# Ematches.net
KiCad netlist of a schematic drawn in Altium Designer
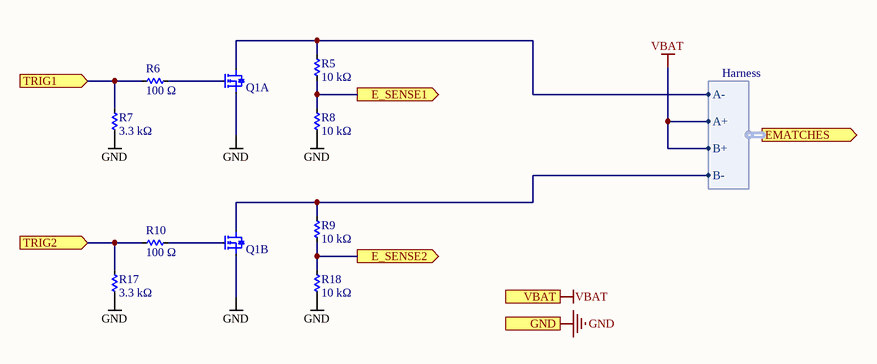
[diagram p0: Ematches.SchDoc]

(export (version "E")
  (design (tool "Eeschema 10.0.6"))
  (components
    (comp (ref "Q1")
      (value "Symbol")
      (footprint "POWERPAK_1212-8_DUAL")
      (description "MOSFET 2N-CH 20V 25A PPAK 1212-8")
      (fields
        (field (name "MANUFACTURER") "Vishay Siliconix")
        (field (name "MANUFACTURER PART NUMBER") "SI7232DN-T1-GE3")
      )
      (libsource (lib "Stanford Student Space Initiative") (part "Symbol"))
    )
    (comp (ref "R5")
      (value "311-10.0KHRCT-ND")
      (footprint "R0603")
      (description "RES SMD 10K OHM 1% 1/10W 0603")
      (fields
        (field (name "MANUFACTURER PART NUMBER") "RC0603FR-0710KL")
        (field (name "MANUFACTURER") "Yageo")
        (field (name "RESISTANCE") "10 kΩ")
      )
      (libsource (lib "Stanford Student Space Initiative") (part "__template_resistor"))
    )
    (comp (ref "R6")
      (value "311-100HRCT-ND")
      (footprint "R0603")
      (description "RES SMD 100 OHM 1% 1/10W 0603")
      (fields
        (field (name "MANUFACTURER PART NUMBER") "RC0603FR-07100RL")
        (field (name "MANUFACTURER") "Yageo")
        (field (name "RESISTANCE") "100 Ω")
      )
      (libsource (lib "Stanford Student Space Initiative") (part "__template_resistor"))
    )
    (comp (ref "R7")
      (value "311-3.30KHRCT-ND")
      (footprint "R0603")
      (description "RES SMD 3.3K OHM 1% 1/10W 0603")
      (fields
        (field (name "MANUFACTURER PART NUMBER") "RC0603FR-073K3L")
        (field (name "MANUFACTURER") "Yageo")
        (field (name "RESISTANCE") "3.3 kΩ")
      )
      (libsource (lib "Stanford Student Space Initiative") (part "__template_resistor"))
    )
    (comp (ref "R8")
      (value "311-10.0KHRCT-ND")
      (footprint "R0603")
      (description "RES SMD 10K OHM 1% 1/10W 0603")
      (fields
        (field (name "MANUFACTURER PART NUMBER") "RC0603FR-0710KL")
        (field (name "MANUFACTURER") "Yageo")
        (field (name "RESISTANCE") "10 kΩ")
      )
      (libsource (lib "Stanford Student Space Initiative") (part "__template_resistor"))
    )
    (comp (ref "R9")
      (value "311-10.0KHRCT-ND")
      (footprint "R0603")
      (description "RES SMD 10K OHM 1% 1/10W 0603")
      (fields
        (field (name "MANUFACTURER PART NUMBER") "RC0603FR-0710KL")
        (field (name "MANUFACTURER") "Yageo")
        (field (name "RESISTANCE") "10 kΩ")
      )
      (libsource (lib "Stanford Student Space Initiative") (part "__template_resistor"))
    )
    (comp (ref "R10")
      (value "311-100HRCT-ND")
      (footprint "R0603")
      (description "RES SMD 100 OHM 1% 1/10W 0603")
      (fields
        (field (name "MANUFACTURER PART NUMBER") "RC0603FR-07100RL")
        (field (name "MANUFACTURER") "Yageo")
        (field (name "RESISTANCE") "100 Ω")
      )
      (libsource (lib "Stanford Student Space Initiative") (part "__template_resistor"))
    )
    (comp (ref "R17")
      (value "311-3.30KHRCT-ND")
      (footprint "R0603")
      (description "RES SMD 3.3K OHM 1% 1/10W 0603")
      (fields
        (field (name "MANUFACTURER PART NUMBER") "RC0603FR-073K3L")
        (field (name "MANUFACTURER") "Yageo")
        (field (name "RESISTANCE") "3.3 kΩ")
      )
      (libsource (lib "Stanford Student Space Initiative") (part "__template_resistor"))
    )
    (comp (ref "R18")
      (value "311-10.0KHRCT-ND")
      (footprint "R0603")
      (description "RES SMD 10K OHM 1% 1/10W 0603")
      (fields
        (field (name "MANUFACTURER PART NUMBER") "RC0603FR-0710KL")
        (field (name "MANUFACTURER") "Yageo")
        (field (name "RESISTANCE") "10 kΩ")
      )
      (libsource (lib "Stanford Student Space Initiative") (part "__template_resistor"))
    )
  )
  (nets
    (net (code "2") (name "/E_SENSE1") (class "Default")
      (node (ref "R5") (pin "2") (pintype "passive"))
      (node (ref "R8") (pin "1") (pintype "passive"))
    )
    (net (code "3") (name "/E_SENSE2") (class "Default")
      (node (ref "R18") (pin "1") (pintype "passive"))
      (node (ref "R9") (pin "2") (pintype "passive"))
    )
    (net (code "4") (name "/TRIG1") (class "Default")
      (node (ref "R6") (pin "1") (pintype "passive"))
      (node (ref "R7") (pin "2") (pintype "passive"))
    )
    (net (code "5") (name "/TRIG2") (class "Default")
      (node (ref "R10") (pin "1") (pintype "passive"))
      (node (ref "R17") (pin "2") (pintype "passive"))
    )
    (net (code "7") (name "GND") (class "Default")
      (node (ref "Q1") (pin "1") (pintype "passive"))
      (node (ref "Q1") (pin "3") (pintype "passive"))
      (node (ref "R17") (pin "1") (pintype "passive"))
      (node (ref "R18") (pin "2") (pintype "passive"))
      (node (ref "R7") (pin "1") (pintype "passive"))
      (node (ref "R8") (pin "2") (pintype "passive"))
    )
    (net (code "8") (name "Net-(Q1-Pad2)") (class "Default")
      (node (ref "Q1") (pin "2") (pintype "passive"))
      (node (ref "R6") (pin "2") (pintype "passive"))
    )
    (net (code "9") (name "Net-(Q1-Pad4)") (class "Default")
      (node (ref "Q1") (pin "4") (pintype "passive"))
      (node (ref "R10") (pin "2") (pintype "passive"))
    )
    (net (code "10") (name "Net-(Q1-Pad5)") (class "Default")
      (node (ref "Q1") (pin "5") (pintype "passive"))
      (node (ref "R9") (pin "1") (pintype "passive"))
    )
    (net (code "11") (name "Net-(Q1-Pad7)") (class "Default")
      (node (ref "Q1") (pin "7") (pintype "passive"))
      (node (ref "R5") (pin "1") (pintype "passive"))
    )
  )
)
